# PIC_PCB.net
KiCad netlist of a schematic drawn in EAGLE
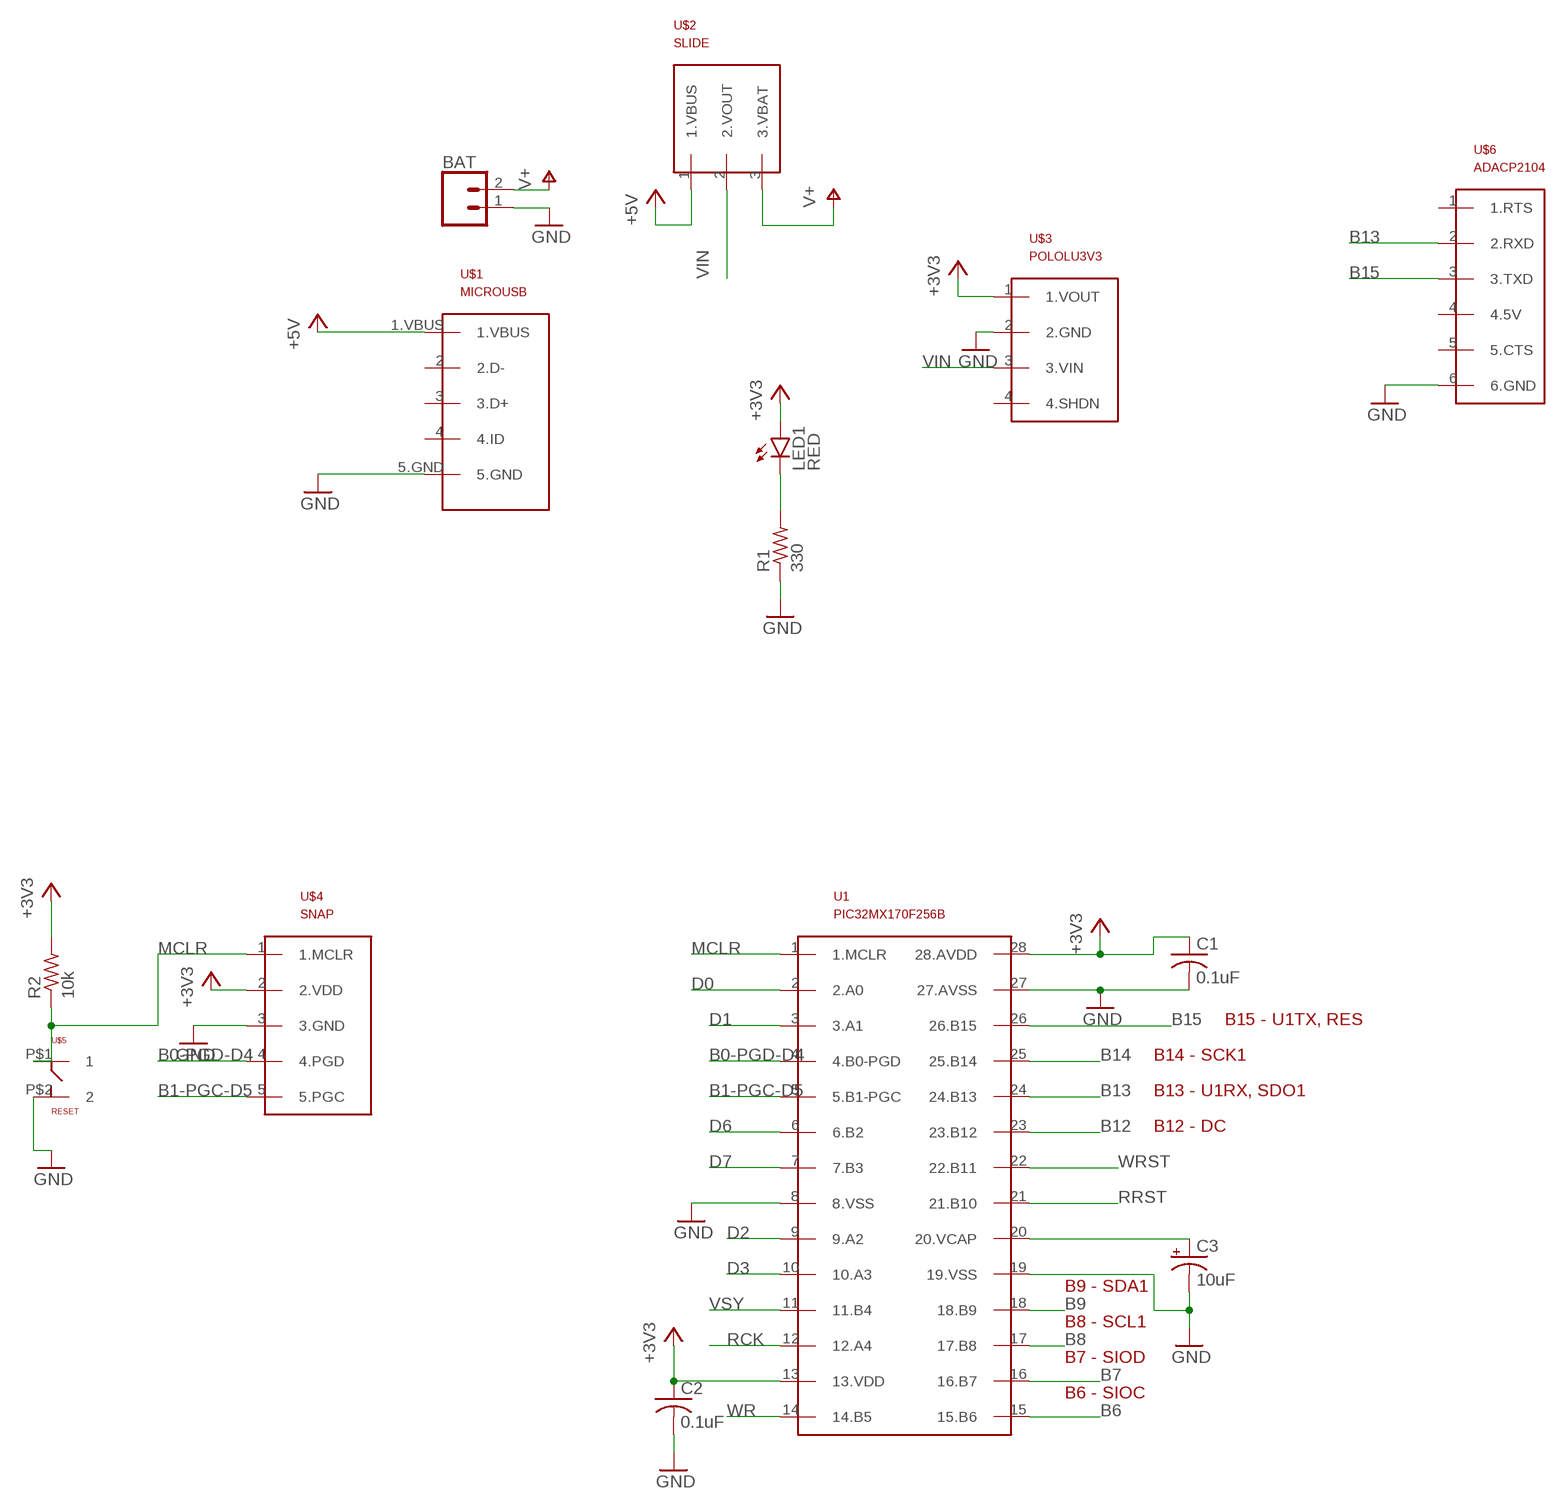
[diagram p0: schematic, sheet 1, part 1 of 2]
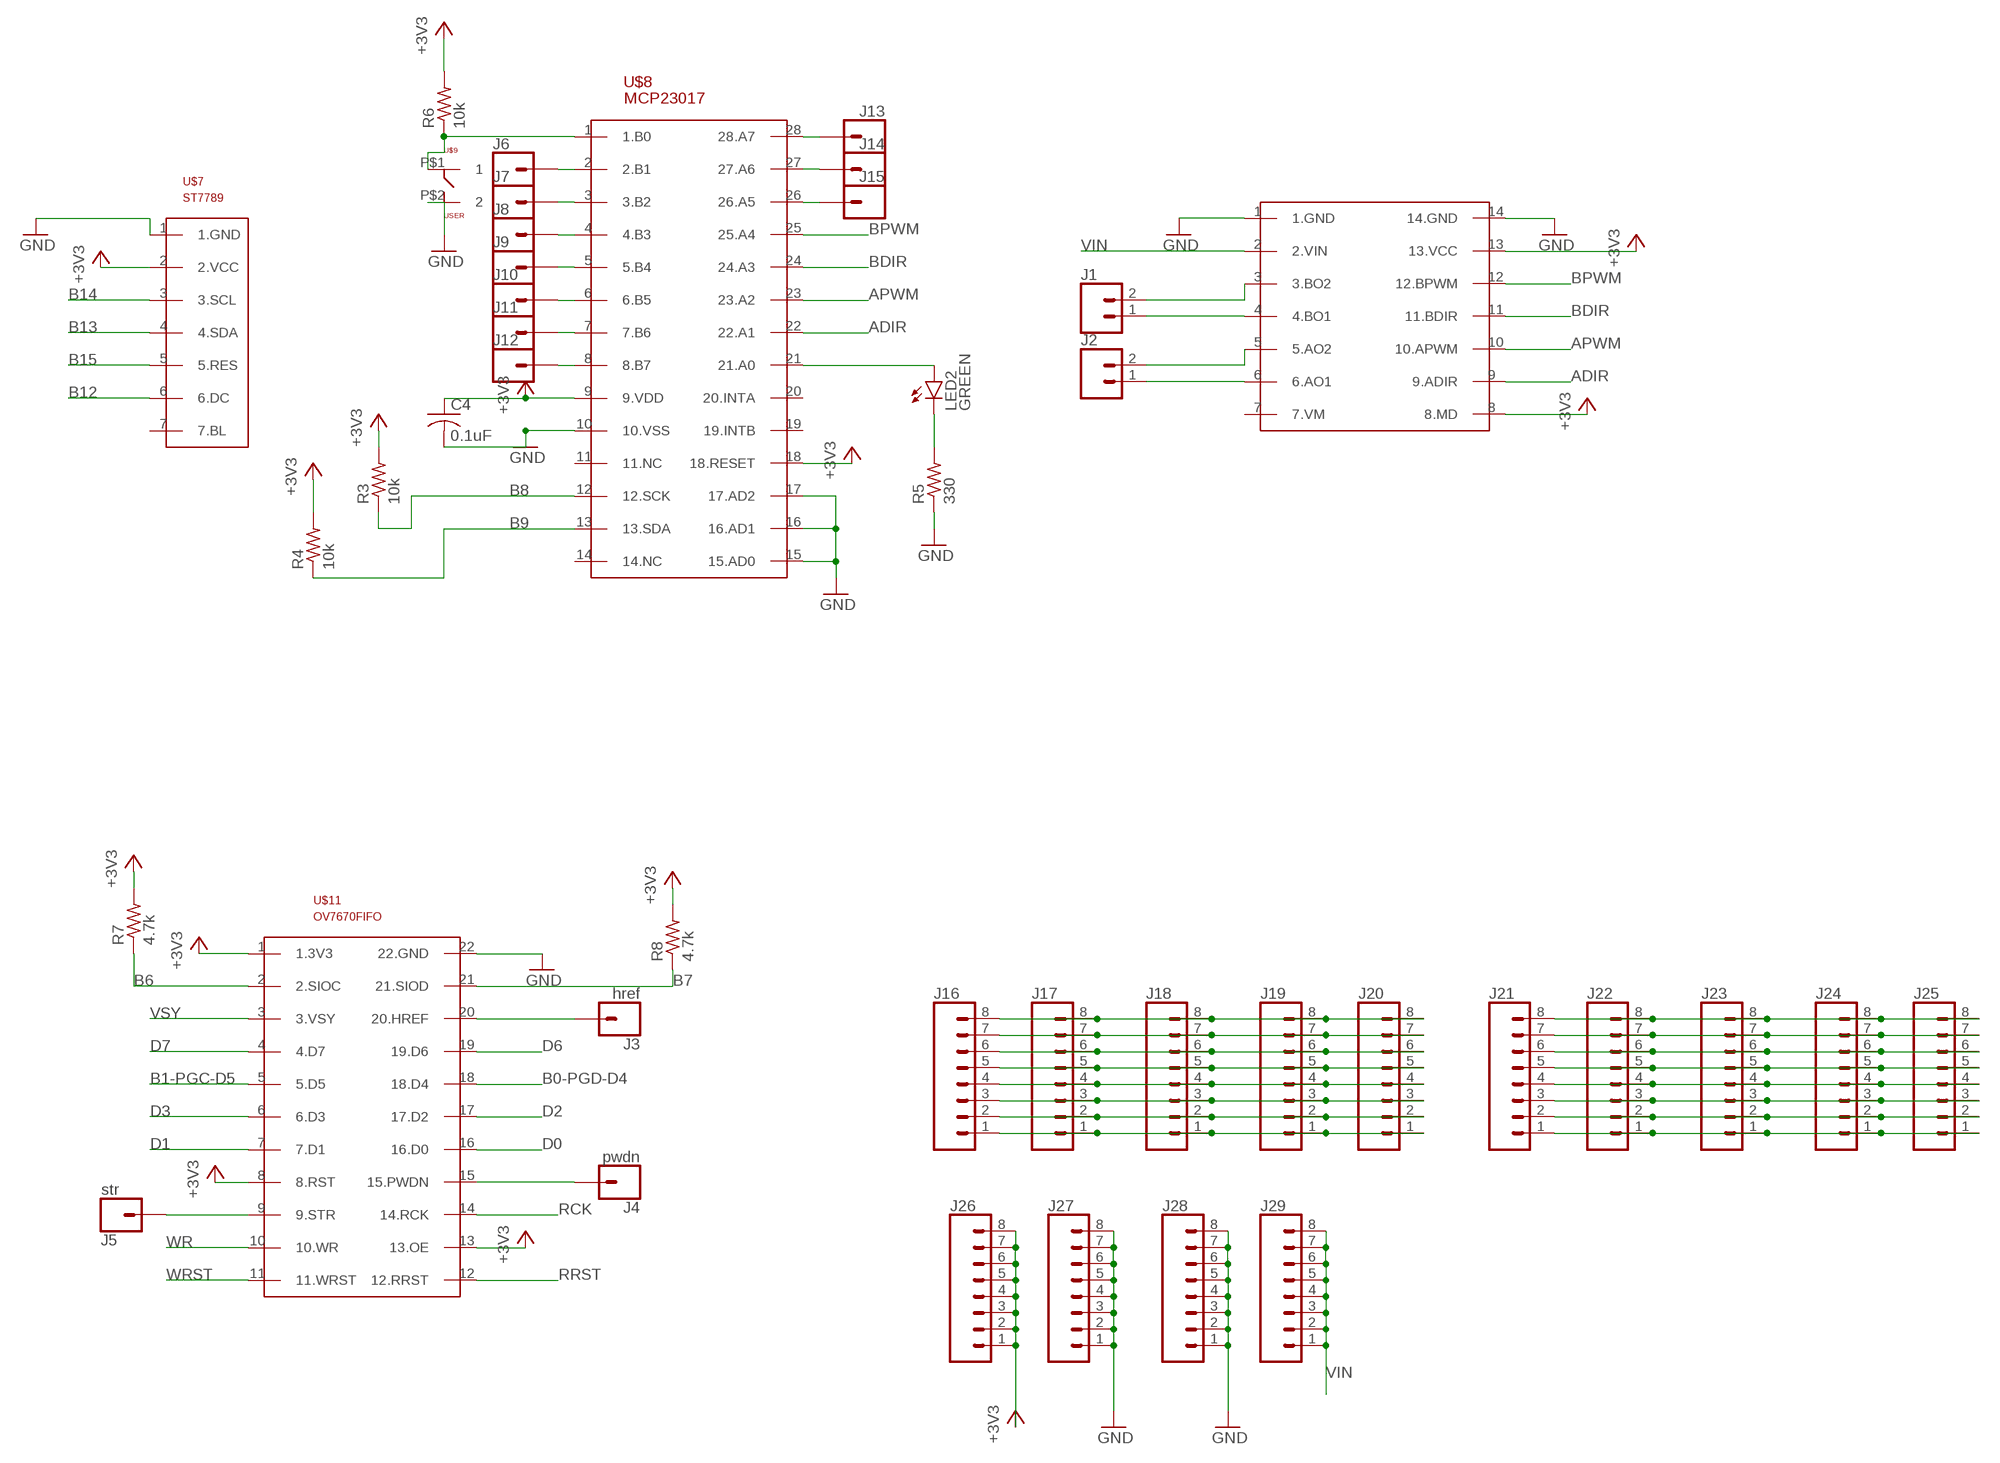
[diagram p1: schematic, sheet 1, part 2 of 2]

(export (version "E")
  (design (tool "Eeschema 10.0.6"))
  (components
    (comp (ref "BAT")
      (value "CONN_02")
      (footprint "eagle-import:1X02")
      (libsource (lib "eagle-import") (part "CONN_02"))
    )
    (comp (ref "C1")
      (value "0.1uF")
      (footprint "eagle-import:C025-030X050")
      (libsource (lib "eagle-import") (part "C-US025-030X050"))
    )
    (comp (ref "C2")
      (value "0.1uF")
      (footprint "eagle-import:C025-030X050")
      (libsource (lib "eagle-import") (part "C-US025-030X050"))
    )
    (comp (ref "C3")
      (value "10uF")
      (footprint "eagle-import:B45181B")
      (libsource (lib "eagle-import") (part "CPOL-USB45181B"))
    )
    (comp (ref "C4")
      (value "0.1uF")
      (footprint "eagle-import:C025-030X050")
      (libsource (lib "eagle-import") (part "C-US025-030X050"))
    )
    (comp (ref "J1")
      (value "CONN_02")
      (footprint "eagle-import:1X02")
      (libsource (lib "eagle-import") (part "CONN_02"))
    )
    (comp (ref "J2")
      (value "CONN_02")
      (footprint "eagle-import:1X02")
      (libsource (lib "eagle-import") (part "CONN_02"))
    )
    (comp (ref "J3")
      (value "href")
      (footprint "eagle-import:1X01")
      (libsource (lib "eagle-import") (part "CONN_01"))
    )
    (comp (ref "J4")
      (value "pwdn")
      (footprint "eagle-import:1X01")
      (libsource (lib "eagle-import") (part "CONN_01"))
    )
    (comp (ref "J5")
      (value "str")
      (footprint "eagle-import:1X01")
      (libsource (lib "eagle-import") (part "CONN_01"))
    )
    (comp (ref "J6")
      (value "CONN_01")
      (footprint "eagle-import:1X01")
      (libsource (lib "eagle-import") (part "CONN_01"))
    )
    (comp (ref "J7")
      (value "CONN_01")
      (footprint "eagle-import:1X01")
      (libsource (lib "eagle-import") (part "CONN_01"))
    )
    (comp (ref "J8")
      (value "CONN_01")
      (footprint "eagle-import:1X01")
      (libsource (lib "eagle-import") (part "CONN_01"))
    )
    (comp (ref "J9")
      (value "CONN_01")
      (footprint "eagle-import:1X01")
      (libsource (lib "eagle-import") (part "CONN_01"))
    )
    (comp (ref "J10")
      (value "CONN_01")
      (footprint "eagle-import:1X01")
      (libsource (lib "eagle-import") (part "CONN_01"))
    )
    (comp (ref "J11")
      (value "CONN_01")
      (footprint "eagle-import:1X01")
      (libsource (lib "eagle-import") (part "CONN_01"))
    )
    (comp (ref "J12")
      (value "CONN_01")
      (footprint "eagle-import:1X01")
      (libsource (lib "eagle-import") (part "CONN_01"))
    )
    (comp (ref "J13")
      (value "CONN_01")
      (footprint "eagle-import:1X01")
      (libsource (lib "eagle-import") (part "CONN_01"))
    )
    (comp (ref "J14")
      (value "CONN_01")
      (footprint "eagle-import:1X01")
      (libsource (lib "eagle-import") (part "CONN_01"))
    )
    (comp (ref "J15")
      (value "CONN_01")
      (footprint "eagle-import:1X01")
      (libsource (lib "eagle-import") (part "CONN_01"))
    )
    (comp (ref "J16")
      (value "CONN_08\"")
      (footprint "eagle-import:1X08")
      (libsource (lib "eagle-import") (part "CONN_08{dblquote}"))
    )
    (comp (ref "J17")
      (value "CONN_08\"")
      (footprint "eagle-import:1X08")
      (libsource (lib "eagle-import") (part "CONN_08{dblquote}"))
    )
    (comp (ref "J18")
      (value "CONN_08\"")
      (footprint "eagle-import:1X08")
      (libsource (lib "eagle-import") (part "CONN_08{dblquote}"))
    )
    (comp (ref "J19")
      (value "CONN_08\"")
      (footprint "eagle-import:1X08")
      (libsource (lib "eagle-import") (part "CONN_08{dblquote}"))
    )
    (comp (ref "J20")
      (value "CONN_08\"")
      (footprint "eagle-import:1X08")
      (libsource (lib "eagle-import") (part "CONN_08{dblquote}"))
    )
    (comp (ref "J21")
      (value "CONN_08\"")
      (footprint "eagle-import:1X08")
      (libsource (lib "eagle-import") (part "CONN_08{dblquote}"))
    )
    (comp (ref "J22")
      (value "CONN_08\"")
      (footprint "eagle-import:1X08")
      (libsource (lib "eagle-import") (part "CONN_08{dblquote}"))
    )
    (comp (ref "J23")
      (value "CONN_08\"")
      (footprint "eagle-import:1X08")
      (libsource (lib "eagle-import") (part "CONN_08{dblquote}"))
    )
    (comp (ref "J24")
      (value "CONN_08\"")
      (footprint "eagle-import:1X08")
      (libsource (lib "eagle-import") (part "CONN_08{dblquote}"))
    )
    (comp (ref "J25")
      (value "CONN_08\"")
      (footprint "eagle-import:1X08")
      (libsource (lib "eagle-import") (part "CONN_08{dblquote}"))
    )
    (comp (ref "J26")
      (value "CONN_08\"")
      (footprint "eagle-import:1X08")
      (libsource (lib "eagle-import") (part "CONN_08{dblquote}"))
    )
    (comp (ref "J27")
      (value "CONN_08\"")
      (footprint "eagle-import:1X08")
      (libsource (lib "eagle-import") (part "CONN_08{dblquote}"))
    )
    (comp (ref "J28")
      (value "CONN_08\"")
      (footprint "eagle-import:1X08")
      (libsource (lib "eagle-import") (part "CONN_08{dblquote}"))
    )
    (comp (ref "J29")
      (value "CONN_08\"")
      (footprint "eagle-import:1X08")
      (libsource (lib "eagle-import") (part "CONN_08{dblquote}"))
    )
    (comp (ref "LED1")
      (value "RED")
      (footprint "eagle-import:LED3MM")
      (libsource (lib "eagle-import") (part "LED3MM"))
    )
    (comp (ref "LED2")
      (value "GREEN")
      (footprint "eagle-import:LED3MM")
      (libsource (lib "eagle-import") (part "LED3MM"))
    )
    (comp (ref "R1")
      (value "330")
      (footprint "eagle-import:0207_10")
      (libsource (lib "eagle-import") (part "R-US_0207/10"))
    )
    (comp (ref "R2")
      (value "10k")
      (footprint "eagle-import:0207_10")
      (libsource (lib "eagle-import") (part "R-US_0207/10"))
    )
    (comp (ref "R3")
      (value "10k")
      (footprint "eagle-import:0207_10")
      (libsource (lib "eagle-import") (part "R-US_0207/10"))
    )
    (comp (ref "R4")
      (value "10k")
      (footprint "eagle-import:0207_10")
      (libsource (lib "eagle-import") (part "R-US_0207/10"))
    )
    (comp (ref "R5")
      (value "330")
      (footprint "eagle-import:0207_10")
      (libsource (lib "eagle-import") (part "R-US_0207/10"))
    )
    (comp (ref "R6")
      (value "10k")
      (footprint "eagle-import:0207_10")
      (libsource (lib "eagle-import") (part "R-US_0207/10"))
    )
    (comp (ref "R7")
      (value "4.7k")
      (footprint "eagle-import:0207_10")
      (libsource (lib "eagle-import") (part "R-US_0207/10"))
    )
    (comp (ref "R8")
      (value "4.7k")
      (footprint "eagle-import:0207_10")
      (libsource (lib "eagle-import") (part "R-US_0207/10"))
    )
    (comp (ref "U$1")
      (value "MICROUSB")
      (footprint "eagle-import:MICROUSB")
      (libsource (lib "eagle-import") (part "MICROUSB"))
    )
    (comp (ref "U$2")
      (value "SLIDE")
      (footprint "eagle-import:SLIDE")
      (libsource (lib "eagle-import") (part "SLIDE"))
    )
    (comp (ref "U$3")
      (value "POLOLU3V3")
      (footprint "eagle-import:POLOLU3V3")
      (libsource (lib "eagle-import") (part "POLOLU3V3"))
    )
    (comp (ref "U$4")
      (value "SNAP")
      (footprint "eagle-import:SNAP")
      (libsource (lib "eagle-import") (part "SNAP"))
    )
    (comp (ref "U$5")
      (value "RESET")
      (footprint "eagle-import:PUSH")
      (libsource (lib "eagle-import") (part "PUSH"))
    )
    (comp (ref "U$6")
      (value "ADACP2104")
      (footprint "eagle-import:ADACP2104")
      (libsource (lib "eagle-import") (part "ADACP2104"))
    )
    (comp (ref "U$7")
      (value "ST7789")
      (footprint "eagle-import:ST7789")
      (libsource (lib "eagle-import") (part "ST7789"))
    )
    (comp (ref "U$8")
      (value "MCP23017")
      (footprint "eagle-import:MCP23017")
      (libsource (lib "eagle-import") (part "MCP23017"))
    )
    (comp (ref "U$9")
      (value "USER")
      (footprint "eagle-import:PUSH")
      (libsource (lib "eagle-import") (part "PUSH"))
    )
    (comp (ref "U$10")
      (value "POLOLUDRV8835")
      (footprint "eagle-import:POLOLUDRV8835")
      (libsource (lib "eagle-import") (part "POLOLUDRV8835"))
    )
    (comp (ref "U$11")
      (value "OV7670FIFO")
      (footprint "eagle-import:OV7670FIFO")
      (libsource (lib "eagle-import") (part "OV7670FIFO"))
    )
    (comp (ref "U1")
      (value "PIC32MX170F256B")
      (footprint "eagle-import:DIL28-3")
      (libsource (lib "eagle-import") (part "PIC32MX170F256B"))
    )
  )
  (nets
    (net (code "1") (name "+3V3") (class "Default")
      (node (ref "C1") (pin "1") (pinfunction "1_1") (pintype "passive"))
      (node (ref "C2") (pin "1") (pinfunction "1_1") (pintype "passive"))
      (node (ref "C4") (pin "1") (pinfunction "1_1") (pintype "passive"))
      (node (ref "J26") (pin "1") (pinfunction "1_1") (pintype "passive"))
      (node (ref "J26") (pin "2") (pinfunction "2_2") (pintype "passive"))
      (node (ref "J26") (pin "3") (pinfunction "3_3") (pintype "passive"))
      (node (ref "J26") (pin "4") (pinfunction "4_4") (pintype "passive"))
      (node (ref "J26") (pin "5") (pinfunction "5_5") (pintype "passive"))
      (node (ref "J26") (pin "6") (pinfunction "6_6") (pintype "passive"))
      (node (ref "J26") (pin "7") (pinfunction "7_7") (pintype "passive"))
      (node (ref "J26") (pin "8") (pinfunction "8_8") (pintype "passive"))
      (node (ref "LED1") (pin "A") (pinfunction "A_A") (pintype "passive"))
      (node (ref "R2") (pin "2") (pinfunction "2_2") (pintype "passive"))
      (node (ref "R3") (pin "2") (pinfunction "2_2") (pintype "passive"))
      (node (ref "R4") (pin "2") (pinfunction "2_2") (pintype "passive"))
      (node (ref "R6") (pin "2") (pinfunction "2_2") (pintype "passive"))
      (node (ref "R7") (pin "2") (pinfunction "2_2") (pintype "passive"))
      (node (ref "R8") (pin "2") (pinfunction "2_2") (pintype "passive"))
      (node (ref "U$10") (pin "13") (pinfunction "13.VCC_13") (pintype "bidirectional"))
      (node (ref "U$10") (pin "8") (pinfunction "8.MD_8") (pintype "bidirectional"))
      (node (ref "U$11") (pin "1") (pinfunction "1.3V3_1") (pintype "bidirectional"))
      (node (ref "U$11") (pin "13") (pinfunction "13.OE_13") (pintype "bidirectional"))
      (node (ref "U$11") (pin "8") (pinfunction "8.RST_8") (pintype "bidirectional"))
      (node (ref "U$3") (pin "1") (pinfunction "1.VOUT_1") (pintype "bidirectional"))
      (node (ref "U$4") (pin "2") (pinfunction "2.VDD_2") (pintype "bidirectional"))
      (node (ref "U$7") (pin "2") (pinfunction "2.VCC_2") (pintype "bidirectional"))
      (node (ref "U$8") (pin "18") (pinfunction "18.RESET_18") (pintype "bidirectional"))
      (node (ref "U$8") (pin "9") (pinfunction "9.VDD_9") (pintype "bidirectional"))
      (node (ref "U1") (pin "13") (pinfunction "13.VDD_13") (pintype "bidirectional"))
      (node (ref "U1") (pin "28") (pinfunction "28.AVDD_28") (pintype "bidirectional"))
    )
    (net (code "2") (name "+5V") (class "Default")
      (node (ref "U$1") (pin "1.VBUS") (pinfunction "1.VBUS_1.VBUS") (pintype "bidirectional"))
      (node (ref "U$2") (pin "1") (pinfunction "1.VBUS_1") (pintype "bidirectional"))
    )
    (net (code "3") (name "/ADIR") (class "Default")
      (node (ref "U$10") (pin "9") (pinfunction "9.ADIR_9") (pintype "bidirectional"))
      (node (ref "U$8") (pin "22") (pinfunction "22.A1_22") (pintype "bidirectional"))
    )
    (net (code "4") (name "/APWM") (class "Default")
      (node (ref "U$10") (pin "10") (pinfunction "10.APWM_10") (pintype "bidirectional"))
      (node (ref "U$8") (pin "23") (pinfunction "23.A2_23") (pintype "bidirectional"))
    )
    (net (code "5") (name "/B0-PGD-D4") (class "Default")
      (node (ref "U$11") (pin "18") (pinfunction "18.D4_18") (pintype "bidirectional"))
      (node (ref "U$4") (pin "4") (pinfunction "4.PGD_4") (pintype "bidirectional"))
      (node (ref "U1") (pin "4") (pinfunction "4.B0-PGD_4") (pintype "bidirectional"))
    )
    (net (code "6") (name "/B1-PGC-D5") (class "Default")
      (node (ref "U$11") (pin "5") (pinfunction "5.D5_5") (pintype "bidirectional"))
      (node (ref "U$4") (pin "5") (pinfunction "5.PGC_5") (pintype "bidirectional"))
      (node (ref "U1") (pin "5") (pinfunction "5.B1-PGC_5") (pintype "bidirectional"))
    )
    (net (code "7") (name "/B6") (class "Default")
      (node (ref "R7") (pin "1") (pinfunction "1_1") (pintype "passive"))
      (node (ref "U$11") (pin "2") (pinfunction "2.SIOC_2") (pintype "bidirectional"))
      (node (ref "U1") (pin "15") (pinfunction "15.B6_15") (pintype "bidirectional"))
    )
    (net (code "8") (name "/B7") (class "Default")
      (node (ref "R8") (pin "1") (pinfunction "1_1") (pintype "passive"))
      (node (ref "U$11") (pin "21") (pinfunction "21.SIOD_21") (pintype "bidirectional"))
      (node (ref "U1") (pin "16") (pinfunction "16.B7_16") (pintype "bidirectional"))
    )
    (net (code "9") (name "/B8") (class "Default")
      (node (ref "R3") (pin "1") (pinfunction "1_1") (pintype "passive"))
      (node (ref "U$8") (pin "12") (pinfunction "12.SCK_12") (pintype "bidirectional"))
      (node (ref "U1") (pin "17") (pinfunction "17.B8_17") (pintype "bidirectional"))
    )
    (net (code "10") (name "/B9") (class "Default")
      (node (ref "R4") (pin "1") (pinfunction "1_1") (pintype "passive"))
      (node (ref "U$8") (pin "13") (pinfunction "13.SDA_13") (pintype "bidirectional"))
      (node (ref "U1") (pin "18") (pinfunction "18.B9_18") (pintype "bidirectional"))
    )
    (net (code "11") (name "/B12") (class "Default")
      (node (ref "U$7") (pin "6") (pinfunction "6.DC_6") (pintype "bidirectional"))
      (node (ref "U1") (pin "23") (pinfunction "23.B12_23") (pintype "bidirectional"))
    )
    (net (code "12") (name "/B13") (class "Default")
      (node (ref "U$6") (pin "2") (pinfunction "2.RXD_2") (pintype "bidirectional"))
      (node (ref "U$7") (pin "4") (pinfunction "4.SDA_4") (pintype "bidirectional"))
      (node (ref "U1") (pin "24") (pinfunction "24.B13_24") (pintype "bidirectional"))
    )
    (net (code "13") (name "/B14") (class "Default")
      (node (ref "U$7") (pin "3") (pinfunction "3.SCL_3") (pintype "bidirectional"))
      (node (ref "U1") (pin "25") (pinfunction "25.B14_25") (pintype "bidirectional"))
    )
    (net (code "14") (name "/B15") (class "Default")
      (node (ref "U$6") (pin "3") (pinfunction "3.TXD_3") (pintype "bidirectional"))
      (node (ref "U$7") (pin "5") (pinfunction "5.RES_5") (pintype "bidirectional"))
      (node (ref "U1") (pin "26") (pinfunction "26.B15_26") (pintype "bidirectional"))
    )
    (net (code "15") (name "/BDIR") (class "Default")
      (node (ref "U$10") (pin "11") (pinfunction "11.BDIR_11") (pintype "bidirectional"))
      (node (ref "U$8") (pin "24") (pinfunction "24.A3_24") (pintype "bidirectional"))
    )
    (net (code "16") (name "/BPWM") (class "Default")
      (node (ref "U$10") (pin "12") (pinfunction "12.BPWM_12") (pintype "bidirectional"))
      (node (ref "U$8") (pin "25") (pinfunction "25.A4_25") (pintype "bidirectional"))
    )
    (net (code "17") (name "/D0") (class "Default")
      (node (ref "U$11") (pin "16") (pinfunction "16.D0_16") (pintype "bidirectional"))
      (node (ref "U1") (pin "2") (pinfunction "2.A0_2") (pintype "bidirectional"))
    )
    (net (code "18") (name "/D1") (class "Default")
      (node (ref "U$11") (pin "7") (pinfunction "7.D1_7") (pintype "bidirectional"))
      (node (ref "U1") (pin "3") (pinfunction "3.A1_3") (pintype "bidirectional"))
    )
    (net (code "19") (name "/D2") (class "Default")
      (node (ref "U$11") (pin "17") (pinfunction "17.D2_17") (pintype "bidirectional"))
      (node (ref "U1") (pin "9") (pinfunction "9.A2_9") (pintype "bidirectional"))
    )
    (net (code "20") (name "/D3") (class "Default")
      (node (ref "U$11") (pin "6") (pinfunction "6.D3_6") (pintype "bidirectional"))
      (node (ref "U1") (pin "10") (pinfunction "10.A3_10") (pintype "bidirectional"))
    )
    (net (code "21") (name "/D6") (class "Default")
      (node (ref "U$11") (pin "19") (pinfunction "19.D6_19") (pintype "bidirectional"))
      (node (ref "U1") (pin "6") (pinfunction "6.B2_6") (pintype "bidirectional"))
    )
    (net (code "22") (name "/D7") (class "Default")
      (node (ref "U$11") (pin "4") (pinfunction "4.D7_4") (pintype "bidirectional"))
      (node (ref "U1") (pin "7") (pinfunction "7.B3_7") (pintype "bidirectional"))
    )
    (net (code "23") (name "/MCLR") (class "Default")
      (node (ref "R2") (pin "1") (pinfunction "1_1") (pintype "passive"))
      (node (ref "U$4") (pin "1") (pinfunction "1.MCLR_1") (pintype "bidirectional"))
      (node (ref "U$5") (pin "P$1") (pinfunction "1_P$1") (pintype "bidirectional"))
      (node (ref "U1") (pin "1") (pinfunction "1.MCLR_1") (pintype "bidirectional"))
    )
    (net (code "24") (name "/RCK") (class "Default")
      (node (ref "U$11") (pin "14") (pinfunction "14.RCK_14") (pintype "bidirectional"))
      (node (ref "U1") (pin "12") (pinfunction "12.A4_12") (pintype "bidirectional"))
    )
    (net (code "25") (name "/RRST") (class "Default")
      (node (ref "U$11") (pin "12") (pinfunction "12.RRST_12") (pintype "bidirectional"))
      (node (ref "U1") (pin "21") (pinfunction "21.B10_21") (pintype "bidirectional"))
    )
    (net (code "26") (name "/VIN") (class "Default")
      (node (ref "J29") (pin "1") (pinfunction "1_1") (pintype "passive"))
      (node (ref "J29") (pin "2") (pinfunction "2_2") (pintype "passive"))
      (node (ref "J29") (pin "3") (pinfunction "3_3") (pintype "passive"))
      (node (ref "J29") (pin "4") (pinfunction "4_4") (pintype "passive"))
      (node (ref "J29") (pin "5") (pinfunction "5_5") (pintype "passive"))
      (node (ref "J29") (pin "6") (pinfunction "6_6") (pintype "passive"))
      (node (ref "J29") (pin "7") (pinfunction "7_7") (pintype "passive"))
      (node (ref "J29") (pin "8") (pinfunction "8_8") (pintype "passive"))
      (node (ref "U$10") (pin "2") (pinfunction "2.VIN_2") (pintype "bidirectional"))
      (node (ref "U$2") (pin "2") (pinfunction "2.VOUT_2") (pintype "bidirectional"))
      (node (ref "U$3") (pin "3") (pinfunction "3.VIN_3") (pintype "bidirectional"))
    )
    (net (code "27") (name "/VSY") (class "Default")
      (node (ref "U$11") (pin "3") (pinfunction "3.VSY_3") (pintype "bidirectional"))
      (node (ref "U1") (pin "11") (pinfunction "11.B4_11") (pintype "bidirectional"))
    )
    (net (code "28") (name "/WR") (class "Default")
      (node (ref "U$11") (pin "10") (pinfunction "10.WR_10") (pintype "bidirectional"))
      (node (ref "U1") (pin "14") (pinfunction "14.B5_14") (pintype "bidirectional"))
    )
    (net (code "29") (name "/WRST") (class "Default")
      (node (ref "U$11") (pin "11") (pinfunction "11.WRST_11") (pintype "bidirectional"))
      (node (ref "U1") (pin "22") (pinfunction "22.B11_22") (pintype "bidirectional"))
    )
    (net (code "30") (name "GND") (class "Default")
      (node (ref "BAT") (pin "1") (pinfunction "1_1") (pintype "passive"))
      (node (ref "C1") (pin "2") (pinfunction "2_2") (pintype "passive"))
      (node (ref "C2") (pin "2") (pinfunction "2_2") (pintype "passive"))
      (node (ref "C3") (pin "-") (pinfunction "-_-") (pintype "passive"))
      (node (ref "C4") (pin "2") (pinfunction "2_2") (pintype "passive"))
      (node (ref "J27") (pin "1") (pinfunction "1_1") (pintype "passive"))
      (node (ref "J27") (pin "2") (pinfunction "2_2") (pintype "passive"))
      (node (ref "J27") (pin "3") (pinfunction "3_3") (pintype "passive"))
      (node (ref "J27") (pin "4") (pinfunction "4_4") (pintype "passive"))
      (node (ref "J27") (pin "5") (pinfunction "5_5") (pintype "passive"))
      (node (ref "J27") (pin "6") (pinfunction "6_6") (pintype "passive"))
      (node (ref "J27") (pin "7") (pinfunction "7_7") (pintype "passive"))
      (node (ref "J27") (pin "8") (pinfunction "8_8") (pintype "passive"))
      (node (ref "J28") (pin "1") (pinfunction "1_1") (pintype "passive"))
      (node (ref "J28") (pin "2") (pinfunction "2_2") (pintype "passive"))
      (node (ref "J28") (pin "3") (pinfunction "3_3") (pintype "passive"))
      (node (ref "J28") (pin "4") (pinfunction "4_4") (pintype "passive"))
      (node (ref "J28") (pin "5") (pinfunction "5_5") (pintype "passive"))
      (node (ref "J28") (pin "6") (pinfunction "6_6") (pintype "passive"))
      (node (ref "J28") (pin "7") (pinfunction "7_7") (pintype "passive"))
      (node (ref "J28") (pin "8") (pinfunction "8_8") (pintype "passive"))
      (node (ref "R1") (pin "1") (pinfunction "1_1") (pintype "passive"))
      (node (ref "R5") (pin "1") (pinfunction "1_1") (pintype "passive"))
      (node (ref "U$1") (pin "5.GND") (pinfunction "5.GND_5.GND") (pintype "bidirectional"))
      (node (ref "U$10") (pin "1") (pinfunction "1.GND_1") (pintype "bidirectional"))
      (node (ref "U$10") (pin "14") (pinfunction "14.GND_14") (pintype "bidirectional"))
      (node (ref "U$11") (pin "22") (pinfunction "22.GND_22") (pintype "bidirectional"))
      (node (ref "U$3") (pin "2") (pinfunction "2.GND_2") (pintype "bidirectional"))
      (node (ref "U$4") (pin "3") (pinfunction "3.GND_3") (pintype "bidirectional"))
      (node (ref "U$5") (pin "P$2") (pinfunction "2_P$2") (pintype "bidirectional"))
      (node (ref "U$6") (pin "6") (pinfunction "6.GND_6") (pintype "bidirectional"))
      (node (ref "U$7") (pin "1") (pinfunction "1.GND_1") (pintype "bidirectional"))
      (node (ref "U$8") (pin "10") (pinfunction "10.VSS_10") (pintype "bidirectional"))
      (node (ref "U$8") (pin "15") (pinfunction "15.AD0_15") (pintype "bidirectional"))
      (node (ref "U$8") (pin "16") (pinfunction "16.AD1_16") (pintype "bidirectional"))
      (node (ref "U$8") (pin "17") (pinfunction "17.AD2_17") (pintype "bidirectional"))
      (node (ref "U$9") (pin "P$2") (pinfunction "2_P$2") (pintype "bidirectional"))
      (node (ref "U1") (pin "19") (pinfunction "19.VSS_19") (pintype "bidirectional"))
      (node (ref "U1") (pin "27") (pinfunction "27.AVSS_27") (pintype "bidirectional"))
      (node (ref "U1") (pin "8") (pinfunction "8.VSS_8") (pintype "bidirectional"))
    )
    (net (code "31") (name "Net-(J16-Pad1)") (class "Default")
      (node (ref "J16") (pin "1") (pinfunction "1_1") (pintype "passive"))
      (node (ref "J17") (pin "1") (pinfunction "1_1") (pintype "passive"))
      (node (ref "J18") (pin "1") (pinfunction "1_1") (pintype "passive"))
      (node (ref "J19") (pin "1") (pinfunction "1_1") (pintype "passive"))
      (node (ref "J20") (pin "1") (pinfunction "1_1") (pintype "passive"))
    )
    (net (code "32") (name "Net-(J16-Pad2)") (class "Default")
      (node (ref "J16") (pin "2") (pinfunction "2_2") (pintype "passive"))
      (node (ref "J17") (pin "2") (pinfunction "2_2") (pintype "passive"))
      (node (ref "J18") (pin "2") (pinfunction "2_2") (pintype "passive"))
      (node (ref "J19") (pin "2") (pinfunction "2_2") (pintype "passive"))
      (node (ref "J20") (pin "2") (pinfunction "2_2") (pintype "passive"))
    )
    (net (code "33") (name "Net-(J16-Pad3)") (class "Default")
      (node (ref "J16") (pin "3") (pinfunction "3_3") (pintype "passive"))
      (node (ref "J17") (pin "3") (pinfunction "3_3") (pintype "passive"))
      (node (ref "J18") (pin "3") (pinfunction "3_3") (pintype "passive"))
      (node (ref "J19") (pin "3") (pinfunction "3_3") (pintype "passive"))
      (node (ref "J20") (pin "3") (pinfunction "3_3") (pintype "passive"))
    )
    (net (code "34") (name "Net-(J16-Pad4)") (class "Default")
      (node (ref "J16") (pin "4") (pinfunction "4_4") (pintype "passive"))
      (node (ref "J17") (pin "4") (pinfunction "4_4") (pintype "passive"))
      (node (ref "J18") (pin "4") (pinfunction "4_4") (pintype "passive"))
      (node (ref "J19") (pin "4") (pinfunction "4_4") (pintype "passive"))
      (node (ref "J20") (pin "4") (pinfunction "4_4") (pintype "passive"))
    )
    (net (code "35") (name "Net-(J16-Pad5)") (class "Default")
      (node (ref "J16") (pin "5") (pinfunction "5_5") (pintype "passive"))
      (node (ref "J17") (pin "5") (pinfunction "5_5") (pintype "passive"))
      (node (ref "J18") (pin "5") (pinfunction "5_5") (pintype "passive"))
      (node (ref "J19") (pin "5") (pinfunction "5_5") (pintype "passive"))
      (node (ref "J20") (pin "5") (pinfunction "5_5") (pintype "passive"))
    )
    (net (code "36") (name "Net-(J16-Pad6)") (class "Default")
      (node (ref "J16") (pin "6") (pinfunction "6_6") (pintype "passive"))
      (node (ref "J17") (pin "6") (pinfunction "6_6") (pintype "passive"))
      (node (ref "J18") (pin "6") (pinfunction "6_6") (pintype "passive"))
      (node (ref "J19") (pin "6") (pinfunction "6_6") (pintype "passive"))
      (node (ref "J20") (pin "6") (pinfunction "6_6") (pintype "passive"))
    )
    (net (code "37") (name "Net-(J16-Pad7)") (class "Default")
      (node (ref "J16") (pin "7") (pinfunction "7_7") (pintype "passive"))
      (node (ref "J17") (pin "7") (pinfunction "7_7") (pintype "passive"))
      (node (ref "J18") (pin "7") (pinfunction "7_7") (pintype "passive"))
      (node (ref "J19") (pin "7") (pinfunction "7_7") (pintype "passive"))
      (node (ref "J20") (pin "7") (pinfunction "7_7") (pintype "passive"))
    )
    (net (code "38") (name "Net-(J16-Pad8)") (class "Default")
      (node (ref "J16") (pin "8") (pinfunction "8_8") (pintype "passive"))
      (node (ref "J17") (pin "8") (pinfunction "8_8") (pintype "passive"))
      (node (ref "J18") (pin "8") (pinfunction "8_8") (pintype "passive"))
      (node (ref "J19") (pin "8") (pinfunction "8_8") (pintype "passive"))
      (node (ref "J20") (pin "8") (pinfunction "8_8") (pintype "passive"))
    )
    (net (code "39") (name "Net-(J21-Pad1)") (class "Default")
      (node (ref "J21") (pin "1") (pinfunction "1_1") (pintype "passive"))
      (node (ref "J22") (pin "1") (pinfunction "1_1") (pintype "passive"))
      (node (ref "J23") (pin "1") (pinfunction "1_1") (pintype "passive"))
      (node (ref "J24") (pin "1") (pinfunction "1_1") (pintype "passive"))
      (node (ref "J25") (pin "1") (pinfunction "1_1") (pintype "passive"))
    )
    (net (code "40") (name "Net-(J21-Pad2)") (class "Default")
      (node (ref "J21") (pin "2") (pinfunction "2_2") (pintype "passive"))
      (node (ref "J22") (pin "2") (pinfunction "2_2") (pintype "passive"))
      (node (ref "J23") (pin "2") (pinfunction "2_2") (pintype "passive"))
      (node (ref "J24") (pin "2") (pinfunction "2_2") (pintype "passive"))
      (node (ref "J25") (pin "2") (pinfunction "2_2") (pintype "passive"))
    )
    (net (code "41") (name "Net-(J21-Pad3)") (class "Default")
      (node (ref "J21") (pin "3") (pinfunction "3_3") (pintype "passive"))
      (node (ref "J22") (pin "3") (pinfunction "3_3") (pintype "passive"))
      (node (ref "J23") (pin "3") (pinfunction "3_3") (pintype "passive"))
      (node (ref "J24") (pin "3") (pinfunction "3_3") (pintype "passive"))
      (node (ref "J25") (pin "3") (pinfunction "3_3") (pintype "passive"))
    )
    (net (code "42") (name "Net-(J21-Pad4)") (class "Default")
      (node (ref "J21") (pin "4") (pinfunction "4_4") (pintype "passive"))
      (node (ref "J22") (pin "4") (pinfunction "4_4") (pintype "passive"))
      (node (ref "J23") (pin "4") (pinfunction "4_4") (pintype "passive"))
      (node (ref "J24") (pin "4") (pinfunction "4_4") (pintype "passive"))
      (node (ref "J25") (pin "4") (pinfunction "4_4") (pintype "passive"))
    )
    (net (code "43") (name "Net-(J21-Pad5)") (class "Default")
      (node (ref "J21") (pin "5") (pinfunction "5_5") (pintype "passive"))
      (node (ref "J22") (pin "5") (pinfunction "5_5") (pintype "passive"))
      (node (ref "J23") (pin "5") (pinfunction "5_5") (pintype "passive"))
      (node (ref "J24") (pin "5") (pinfunction "5_5") (pintype "passive"))
      (node (ref "J25") (pin "5") (pinfunction "5_5") (pintype "passive"))
    )
    (net (code "44") (name "Net-(J21-Pad6)") (class "Default")
      (node (ref "J21") (pin "6") (pinfunction "6_6") (pintype "passive"))
      (node (ref "J22") (pin "6") (pinfunction "6_6") (pintype "passive"))
      (node (ref "J23") (pin "6") (pinfunction "6_6") (pintype "passive"))
      (node (ref "J24") (pin "6") (pinfunction "6_6") (pintype "passive"))
      (node (ref "J25") (pin "6") (pinfunction "6_6") (pintype "passive"))
    )
    (net (code "45") (name "Net-(J21-Pad7)") (class "Default")
      (node (ref "J21") (pin "7") (pinfunction "7_7") (pintype "passive"))
      (node (ref "J22") (pin "7") (pinfunction "7_7") (pintype "passive"))
      (node (ref "J23") (pin "7") (pinfunction "7_7") (pintype "passive"))
      (node (ref "J24") (pin "7") (pinfunction "7_7") (pintype "passive"))
      (node (ref "J25") (pin "7") (pinfunction "7_7") (pintype "passive"))
    )
    (net (code "46") (name "Net-(J21-Pad8)") (class "Default")
      (node (ref "J21") (pin "8") (pinfunction "8_8") (pintype "passive"))
      (node (ref "J22") (pin "8") (pinfunction "8_8") (pintype "passive"))
      (node (ref "J23") (pin "8") (pinfunction "8_8") (pintype "passive"))
      (node (ref "J24") (pin "8") (pinfunction "8_8") (pintype "passive"))
      (node (ref "J25") (pin "8") (pinfunction "8_8") (pintype "passive"))
    )
    (net (code "47") (name "Net-(LED1-C)") (class "Default")
      (node (ref "LED1") (pin "K") (pinfunction "C_K") (pintype "passive"))
      (node (ref "R1") (pin "2") (pinfunction "2_2") (pintype "passive"))
    )
    (net (code "48") (name "Net-(LED2-C)") (class "Default")
      (node (ref "LED2") (pin "K") (pinfunction "C_K") (pintype "passive"))
      (node (ref "R5") (pin "2") (pinfunction "2_2") (pintype "passive"))
    )
    (net (code "49") (name "Net-(U$8-1.B0)") (class "Default")
      (node (ref "R6") (pin "1") (pinfunction "1_1") (pintype "passive"))
      (node (ref "U$8") (pin "1") (pinfunction "1.B0_1") (pintype "bidirectional"))
      (node (ref "U$9") (pin "P$1") (pinfunction "1_P$1") (pintype "bidirectional"))
    )
    (net (code "50") (name "Net-(U$8-2.B1)") (class "Default")
      (node (ref "J6") (pin "1") (pinfunction "1_1") (pintype "passive"))
      (node (ref "U$8") (pin "2") (pinfunction "2.B1_2") (pintype "bidirectional"))
    )
    (net (code "51") (name "Net-(U$8-3.B2)") (class "Default")
      (node (ref "J7") (pin "1") (pinfunction "1_1") (pintype "passive"))
      (node (ref "U$8") (pin "3") (pinfunction "3.B2_3") (pintype "bidirectional"))
    )
    (net (code "52") (name "Net-(U$8-4.B3)") (class "Default")
      (node (ref "J8") (pin "1") (pinfunction "1_1") (pintype "passive"))
      (node (ref "U$8") (pin "4") (pinfunction "4.B3_4") (pintype "bidirectional"))
    )
    (net (code "53") (name "Net-(U$8-5.B4)") (class "Default")
      (node (ref "J9") (pin "1") (pinfunction "1_1") (pintype "passive"))
      (node (ref "U$8") (pin "5") (pinfunction "5.B4_5") (pintype "bidirectional"))
    )
    (net (code "54") (name "Net-(U$8-6.B5)") (class "Default")
      (node (ref "J10") (pin "1") (pinfunction "1_1") (pintype "passive"))
      (node (ref "U$8") (pin "6") (pinfunction "6.B5_6") (pintype "bidirectional"))
    )
    (net (code "55") (name "Net-(U$8-7.B6)") (class "Default")
      (node (ref "J11") (pin "1") (pinfunction "1_1") (pintype "passive"))
      (node (ref "U$8") (pin "7") (pinfunction "7.B6_7") (pintype "bidirectional"))
    )
    (net (code "56") (name "Net-(U$8-8.B7)") (class "Default")
      (node (ref "J12") (pin "1") (pinfunction "1_1") (pintype "passive"))
      (node (ref "U$8") (pin "8") (pinfunction "8.B7_8") (pintype "bidirectional"))
    )
    (net (code "57") (name "Net-(U$8-21.A0)") (class "Default")
      (node (ref "LED2") (pin "A") (pinfunction "A_A") (pintype "passive"))
      (node (ref "U$8") (pin "21") (pinfunction "21.A0_21") (pintype "bidirectional"))
    )
    (net (code "58") (name "Net-(U$8-26.A5)") (class "Default")
      (node (ref "J15") (pin "1") (pinfunction "1_1") (pintype "passive"))
      (node (ref "U$8") (pin "26") (pinfunction "26.A5_26") (pintype "bidirectional"))
    )
    (net (code "59") (name "Net-(U$8-27.A6)") (class "Default")
      (node (ref "J14") (pin "1") (pinfunction "1_1") (pintype "passive"))
      (node (ref "U$8") (pin "27") (pinfunction "27.A6_27") (pintype "bidirectional"))
    )
    (net (code "60") (name "Net-(U$8-28.A7)") (class "Default")
      (node (ref "J13") (pin "1") (pinfunction "1_1") (pintype "passive"))
      (node (ref "U$8") (pin "28") (pinfunction "28.A7_28") (pintype "bidirectional"))
    )
    (net (code "61") (name "Net-(U$10-3.BO2)") (class "Default")
      (node (ref "J1") (pin "2") (pinfunction "2_2") (pintype "passive"))
      (node (ref "U$10") (pin "3") (pinfunction "3.BO2_3") (pintype "bidirectional"))
    )
    (net (code "62") (name "Net-(U$10-4.BO1)") (class "Default")
      (node (ref "J1") (pin "1") (pinfunction "1_1") (pintype "passive"))
      (node (ref "U$10") (pin "4") (pinfunction "4.BO1_4") (pintype "bidirectional"))
    )
    (net (code "63") (name "Net-(U$10-5.AO2)") (class "Default")
      (node (ref "J2") (pin "2") (pinfunction "2_2") (pintype "passive"))
      (node (ref "U$10") (pin "5") (pinfunction "5.AO2_5") (pintype "bidirectional"))
    )
    (net (code "64") (name "Net-(U$10-6.AO1)") (class "Default")
      (node (ref "J2") (pin "1") (pinfunction "1_1") (pintype "passive"))
      (node (ref "U$10") (pin "6") (pinfunction "6.AO1_6") (pintype "bidirectional"))
    )
    (net (code "65") (name "Net-(U$11-9.STR)") (class "Default")
      (node (ref "J5") (pin "1") (pinfunction "1_1") (pintype "passive"))
      (node (ref "U$11") (pin "9") (pinfunction "9.STR_9") (pintype "bidirectional"))
    )
    (net (code "66") (name "Net-(U$11-15.PWDN)") (class "Default")
      (node (ref "J4") (pin "1") (pinfunction "1_1") (pintype "passive"))
      (node (ref "U$11") (pin "15") (pinfunction "15.PWDN_15") (pintype "bidirectional"))
    )
    (net (code "67") (name "Net-(U$11-20.HREF)") (class "Default")
      (node (ref "J3") (pin "1") (pinfunction "1_1") (pintype "passive"))
      (node (ref "U$11") (pin "20") (pinfunction "20.HREF_20") (pintype "bidirectional"))
    )
    (net (code "68") (name "Net-(U1-20.VCAP)") (class "Default")
      (node (ref "C3") (pin "+") (pinfunction "+_+") (pintype "passive"))
      (node (ref "U1") (pin "20") (pinfunction "20.VCAP_20") (pintype "bidirectional"))
    )
    (net (code "69") (name "V+") (class "Default")
      (node (ref "BAT") (pin "2") (pinfunction "2_2") (pintype "passive"))
      (node (ref "U$2") (pin "3") (pinfunction "3.VBAT_3") (pintype "bidirectional"))
    )
    (net (code "70") (name "unconnected-(U$1-2.D--Pad2)") (class "Default")
      (node (ref "U$1") (pin "2") (pinfunction "2.D-_2") (pintype "bidirectional"))
    )
    (net (code "71") (name "unconnected-(U$1-3.D+-Pad3)") (class "Default")
      (node (ref "U$1") (pin "3") (pinfunction "3.D+_3") (pintype "bidirectional"))
    )
    (net (code "72") (name "unconnected-(U$1-4.ID-Pad4)") (class "Default")
      (node (ref "U$1") (pin "4") (pinfunction "4.ID_4") (pintype "bidirectional"))
    )
    (net (code "73") (name "unconnected-(U$3-4.SHDN-Pad4)") (class "Default")
      (node (ref "U$3") (pin "4") (pinfunction "4.SHDN_4") (pintype "bidirectional"))
    )
    (net (code "74") (name "unconnected-(U$6-1.RTS-Pad1)") (class "Default")
      (node (ref "U$6") (pin "1") (pinfunction "1.RTS_1") (pintype "bidirectional"))
    )
    (net (code "75") (name "unconnected-(U$6-4.5V-Pad4)") (class "Default")
      (node (ref "U$6") (pin "4") (pinfunction "4.5V_4") (pintype "bidirectional"))
    )
    (net (code "76") (name "unconnected-(U$6-5.CTS-Pad5)") (class "Default")
      (node (ref "U$6") (pin "5") (pinfunction "5.CTS_5") (pintype "bidirectional"))
    )
    (net (code "77") (name "unconnected-(U$7-7.BL-Pad7)") (class "Default")
      (node (ref "U$7") (pin "7") (pinfunction "7.BL_7") (pintype "bidirectional"))
    )
    (net (code "78") (name "unconnected-(U$8-11.NC-Pad11)") (class "Default")
      (node (ref "U$8") (pin "11") (pinfunction "11.NC_11") (pintype "bidirectional"))
    )
    (net (code "79") (name "unconnected-(U$8-14.NC-Pad14)") (class "Default")
      (node (ref "U$8") (pin "14") (pinfunction "14.NC_14") (pintype "bidirectional"))
    )
    (net (code "80") (name "unconnected-(U$8-19.INTB-Pad19)") (class "Default")
      (node (ref "U$8") (pin "19") (pinfunction "19.INTB_19") (pintype "bidirectional"))
    )
    (net (code "81") (name "unconnected-(U$8-20.INTA-Pad20)") (class "Default")
      (node (ref "U$8") (pin "20") (pinfunction "20.INTA_20") (pintype "bidirectional"))
    )
    (net (code "82") (name "unconnected-(U$10-7.VM-Pad7)") (class "Default")
      (node (ref "U$10") (pin "7") (pinfunction "7.VM_7") (pintype "bidirectional"))
    )
  )
)
